# STM32F103T8.net
KiCad netlist of a schematic drawn in Altium Designer
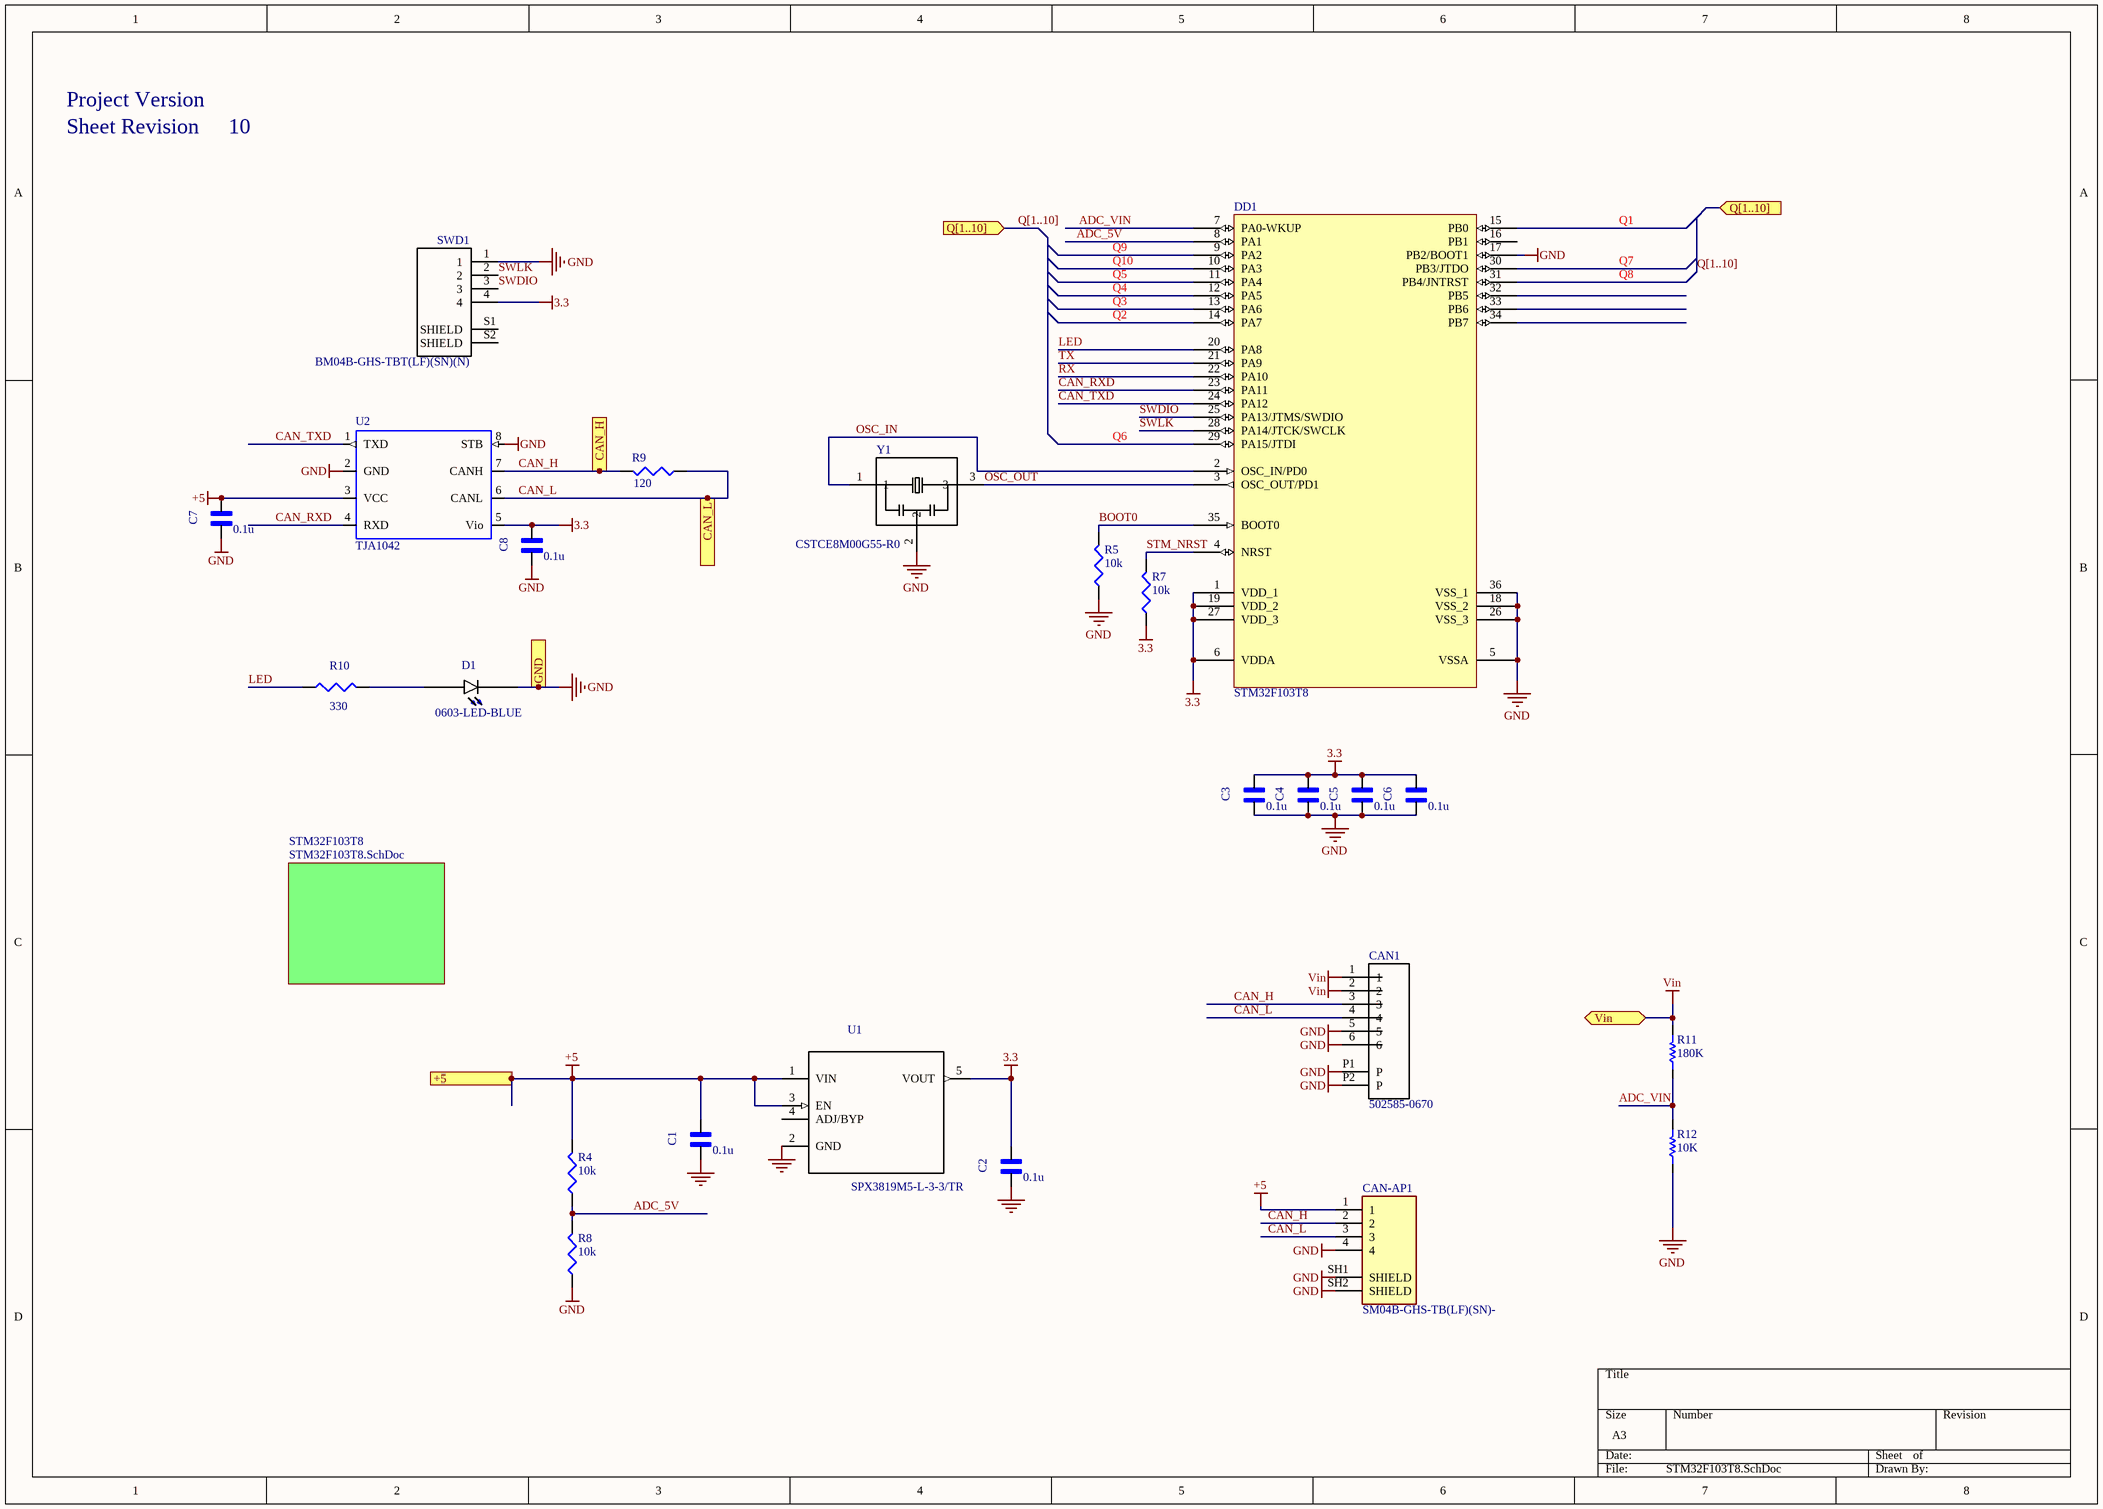
[diagram p0: STM32F103T8.SchDoc]

(export (version "E")
  (design (tool "Eeschema 10.0.6"))
  (components
    (comp (ref "C1")
      (value "0.1u")
      (footprint "*CAPC1608X90")
      (description "Cap Thin Film 0.1uf 50v 0603")
      (fields (field (name "MF") "AVX") (field (name "MP") "GX035C104MAT2-500"))
      (libsource (lib "lib") (part "GX035C104MAT2-500"))
    )
    (comp (ref "C2")
      (value "0.1u")
      (footprint "*CAPC1608X90")
      (description "Cap Thin Film 0.1uf 50v 0603")
      (fields (field (name "MF") "AVX") (field (name "MP") "GX035C104MAT2-500"))
      (libsource (lib "lib") (part "GX035C104MAT2-500"))
    )
    (comp (ref "C3")
      (value "0.1u")
      (footprint "*CAPC1608X90")
      (description "Cap Thin Film 0.1uf 50v 0603")
      (fields (field (name "MF") "AVX") (field (name "MP") "GX035C104MAT2-500 or CL10B104JB8NNNC"))
      (libsource (lib "lib") (part "GX035C104MAT2-500"))
    )
    (comp (ref "C4")
      (value "0.1u")
      (footprint "*CAPC1608X90")
      (description "Cap Thin Film 0.1uf 50v 0603")
      (fields (field (name "MF") "AVX") (field (name "MP") "GX035C104MAT2-500 or CL10B104JB8NNNC"))
      (libsource (lib "lib") (part "GX035C104MAT2-500"))
    )
    (comp (ref "C5")
      (value "0.1u")
      (footprint "*CAPC1608X90")
      (description "Cap Thin Film 0.1uf 50v 0603")
      (fields (field (name "MF") "AVX") (field (name "MP") "GX035C104MAT2-500 or CL10B104JB8NNNC"))
      (libsource (lib "lib") (part "GX035C104MAT2-500"))
    )
    (comp (ref "C6")
      (value "0.1u")
      (footprint "*CAPC1608X90")
      (description "Cap Thin Film 0.1uf 50v 0603")
      (fields (field (name "MF") "AVX") (field (name "MP") "GX035C104MAT2-500 or CL10B104JB8NNNC"))
      (libsource (lib "lib") (part "GX035C104MAT2-500"))
    )
    (comp (ref "C7")
      (value "0.1u")
      (footprint "*CAPC1608X90")
      (description "Cap Thin Film 0.1uf 50v 0603")
      (fields (field (name "MF") "AVX") (field (name "MP") "GX035C104MAT2-500 or CL10B104JB8NNNC"))
      (libsource (lib "lib") (part "GX035C104MAT2-500"))
    )
    (comp (ref "C8")
      (value "0.1u")
      (footprint "*CAPC1608X90")
      (description "Cap Thin Film 0.1uf 50v 0603")
      (fields (field (name "MF") "AVX") (field (name "MP") "GX035C104MAT2-500 or CL10B104JB8NNNC"))
      (libsource (lib "lib") (part "GX035C104MAT2-500"))
    )
    (comp (ref "CAN-AP1")
      (value "SM04B-GHS-TB(LF)(SN)-")
      (footprint "JST_SM04B-GHS-TB(LF)(SN)-")
      (description "Connector Header Surface Mount, Right Angle 4 position 0.049 _1.25mm_")
      (fields (field (name "MP") "SM04B-GHS-TB(LF)(SN)") (field (name "MF") "JST Sales"))
      (libsource (lib "lib") (part "SM04B-GHS-TB(LF)(SN)-"))
    )
    (comp (ref "CAN1")
      (value "502585-0670")
      (footprint "MOLEX_502585-0670")
      (fields (field (name "MF") "Molex"))
      (libsource (lib "lib") (part "502585-0670"))
    )
    (comp (ref "D1")
      (value "0603-LED-BLUE")
      (footprint "*LEDM1608X80_LTE-C1906R-14(Primary)")
      (description "LED IrLED Chip LED 2-Pin SMD T/R")
      (libsource (lib "lib") (part "LTE-C1906R-14"))
    )
    (comp (ref "DD1")
      (value "STM32F103T8")
      (footprint "*QFN50P600X600X100-37N")
      (description "STM32F103T8U6, Микроконтроллер 32BIT ARM 64K FLASH [VFQFPN-36]")
      (fields (field (name "MF") "STM") (field (name "MP") "STM32F103T8U6"))
      (libsource (lib "lib") (part "STM32F103T8"))
    )
    (comp (ref "R4")
      (value "10k")
      (footprint "J1-0603")
      (description "10 kOhms 1 0.1 W 1 10 W Chip Resistor 0603 1608 Metric Thick Film")
      (fields (field (name "MF") "Yageo or NXP") (field (name "MP") "10K 1% 0603"))
      (libsource (lib "CAN_NODE_MINI") (part "RC0603FR-0710KL"))
    )
    (comp (ref "R5")
      (value "10k")
      (footprint "J1-0603")
      (description "10 kOhms 1 0.1 W 1 10 W Chip Resistor 0603 1608 Metric Thick Film")
      (fields (field (name "MF") "Yageo or NXP") (field (name "MP") "10K 1% 0603"))
      (libsource (lib "CAN_NODE_MINI") (part "RC0603FR-0710KL"))
    )
    (comp (ref "R7")
      (value "10k")
      (footprint "J1-0603")
      (description "10 kOhms 1 0.1 W 1 10 W Chip Resistor 0603 1608 Metric Thick Film")
      (fields (field (name "MF") "Yageo or NXP") (field (name "MP") "10K 1% 0603"))
      (libsource (lib "CAN_NODE_MINI") (part "RC0603FR-0710KL"))
    )
    (comp (ref "R8")
      (value "10k")
      (footprint "J1-0603")
      (description "10 kOhms 1 0.1 W 1 10 W Chip Resistor 0603 1608 Metric Thick Film")
      (fields (field (name "MF") "Yageo or NXP") (field (name "MP") "10K 1% 0603"))
      (libsource (lib "CAN_NODE_MINI") (part "RC0603FR-0710KL"))
    )
    (comp (ref "R9")
      (value "120")
      (footprint "J1-0603")
      (description "120 Ohms 1 0.1 W 1 10 W Chip Resistor 0603 1608 Metric Thick Film")
      (fields (field (name "MP") "RC0603FR-07120RL") (field (name "Comment") "Res3"))
      (libsource (lib "Miscellaneous Devices") (part "Res3"))
    )
    (comp (ref "R10")
      (value "330")
      (footprint "J1-0603")
      (description "Resistor")
      (fields (field (name "MP") "RC0603FR-07330RL") (field (name "Comment") "Res3"))
      (libsource (lib "Miscellaneous Devices") (part "Res3"))
    )
    (comp (ref "R11")
      (value "180K")
      (footprint "RES 0603 (1608X06L)")
      (description "Resistor")
      (fields (field (name "TOLERANCE") "5%") (field (name "POWER") "1/8 W"))
      (libsource (lib "R2T Team Library") (part "Resistor"))
    )
    (comp (ref "R12")
      (value "10K")
      (footprint "RES 0603 (1608X06L)")
      (description "Resistor")
      (fields (field (name "TOLERANCE") "5%") (field (name "POWER") "1/8 W"))
      (libsource (lib "R2T Team Library") (part "Resistor"))
    )
    (comp (ref "SWD1")
      (value "BM04B-GHS-TBT(LF)(SN)(N)")
      (footprint "JST_BM04B-GHS-holes")
      (description "Conn Shrouded Header HDR 4 POS 1.25mm Solder ST SMD Reel")
      (fields (field (name "MF") "JST Sales") (field (name "MP") "SM04B-GHS-TB(LF)(SN)"))
      (libsource (lib "lib") (part "BM04B-GHS-TBT(LF)(SN)(N)"))
    )
    (comp (ref "U1")
      (value "SPX3819M5-L-3-3/TR")
      (footprint "*SOT95P280X145-5N")
      (description "Low Dropout Voltage Regulator, Adjustable 0.5A, В±1%, 2.5 to 16 Vin, 5-Pin SOT-23")
      (fields (field (name "MF") "MaxLinear, Inc."))
      (libsource (lib "DC_DC") (part "SPX3819M5-L"))
    )
    (comp (ref "U2")
      (value "TJA1042")
      (footprint "SOT782-1")
      (description "1/1 Transceiver Half CANbus 8-SO")
      (fields (field (name "MF") "NXP USA"))
      (libsource (lib "lib") (part "TJA1042"))
    )
    (comp (ref "Y1")
      (value "CSTCE8M00G55-R0")
      (footprint "*OSC_CSTCE8M00G55-R0")
      (description "Ceramic Resonator 8MHz ??0.5% _Tol_ ??0.2% _Stability_ 33pF 40Ohm 3-Pin CSMD T/R")
      (fields (field (name "MF") "Murata"))
      (libsource (lib "DC_DC") (part "CSTCE8M00G55-R0"))
    )
  )
  (nets
    (net (code "1") (name "+5") (class "Default")
      (node (ref "C1") (pin "1") (pinfunction "1_1") (pintype "passive"))
      (node (ref "C7") (pin "1") (pinfunction "1_1") (pintype "passive"))
      (node (ref "CAN-AP1") (pin "1") (pinfunction "1_1") (pintype "passive"))
      (node (ref "R4") (pin "2") (pinfunction "2_2") (pintype "passive"))
      (node (ref "U1") (pin "1") (pinfunction "VIN_1") (pintype "power_in"))
      (node (ref "U1") (pin "3") (pinfunction "EN_3") (pintype "input"))
      (node (ref "U2") (pin "3") (pinfunction "VCC_3") (pintype "power_in"))
    )
    (net (code "2") (name "/ADC_5V") (class "Default")
      (node (ref "DD1") (pin "8") (pinfunction "PA1_8") (pintype "bidirectional"))
      (node (ref "R4") (pin "1") (pinfunction "1_1") (pintype "passive"))
      (node (ref "R8") (pin "2") (pinfunction "2_2") (pintype "passive"))
    )
    (net (code "3") (name "/ADC_VIN") (class "Default")
      (node (ref "DD1") (pin "7") (pinfunction "PA0-WKUP_7") (pintype "bidirectional"))
      (node (ref "R11") (pin "1") (pinfunction "1_1") (pintype "passive"))
      (node (ref "R12") (pin "2") (pinfunction "2_2") (pintype "passive"))
    )
    (net (code "4") (name "/BOOT0") (class "Default")
      (node (ref "DD1") (pin "35") (pinfunction "BOOT0_35") (pintype "input"))
      (node (ref "R5") (pin "2") (pinfunction "2_2") (pintype "passive"))
    )
    (net (code "5") (name "/CAN_H") (class "Default")
      (node (ref "CAN-AP1") (pin "2") (pinfunction "2_2") (pintype "passive"))
      (node (ref "CAN1") (pin "3") (pinfunction "3_3") (pintype "passive"))
      (node (ref "R9") (pin "2") (pinfunction "2_2") (pintype "passive"))
      (node (ref "U2") (pin "7") (pinfunction "CANH_7") (pintype "bidirectional"))
    )
    (net (code "6") (name "/CAN_L") (class "Default")
      (node (ref "CAN-AP1") (pin "3") (pinfunction "3_3") (pintype "passive"))
      (node (ref "CAN1") (pin "4") (pinfunction "4_4") (pintype "passive"))
      (node (ref "R9") (pin "1") (pinfunction "1_1") (pintype "passive"))
      (node (ref "U2") (pin "6") (pinfunction "CANL_6") (pintype "bidirectional"))
    )
    (net (code "7") (name "/CAN_RXD") (class "Default")
      (node (ref "DD1") (pin "23") (pinfunction "PA11_23") (pintype "bidirectional"))
      (node (ref "U2") (pin "4") (pinfunction "RXD_4") (pintype "bidirectional"))
    )
    (net (code "8") (name "/CAN_TXD") (class "Default")
      (node (ref "DD1") (pin "24") (pinfunction "PA12_24") (pintype "bidirectional"))
      (node (ref "U2") (pin "1") (pinfunction "TXD_1") (pintype "output"))
    )
    (net (code "9") (name "/LED") (class "Default")
      (node (ref "DD1") (pin "20") (pinfunction "PA8_20") (pintype "bidirectional"))
      (node (ref "R10") (pin "1") (pinfunction "1_1") (pintype "passive"))
    )
    (net (code "10") (name "/OSC_IN") (class "Default")
      (node (ref "DD1") (pin "2") (pinfunction "OSC_IN/PD0_2") (pintype "input"))
      (node (ref "Y1") (pin "1") (pinfunction "1_1") (pintype "passive"))
    )
    (net (code "11") (name "/OSC_OUT") (class "Default")
      (node (ref "DD1") (pin "3") (pinfunction "OSC_OUT/PD1_3") (pintype "output"))
      (node (ref "Y1") (pin "3") (pinfunction "3_3") (pintype "passive"))
    )
    (net (code "12") (name "/Q1") (class "Default")
      (node (ref "DD1") (pin "15") (pinfunction "PB0_15") (pintype "bidirectional"))
    )
    (net (code "13") (name "/Q2") (class "Default")
      (node (ref "DD1") (pin "14") (pinfunction "PA7_14") (pintype "bidirectional"))
    )
    (net (code "14") (name "/Q3") (class "Default")
      (node (ref "DD1") (pin "13") (pinfunction "PA6_13") (pintype "bidirectional"))
    )
    (net (code "15") (name "/Q4") (class "Default")
      (node (ref "DD1") (pin "12") (pinfunction "PA5_12") (pintype "bidirectional"))
    )
    (net (code "16") (name "/Q5") (class "Default")
      (node (ref "DD1") (pin "11") (pinfunction "PA4_11") (pintype "bidirectional"))
    )
    (net (code "17") (name "/Q6") (class "Default")
      (node (ref "DD1") (pin "29") (pinfunction "PA15/JTDI_29") (pintype "bidirectional"))
    )
    (net (code "18") (name "/Q7") (class "Default")
      (node (ref "DD1") (pin "30") (pinfunction "PB3/JTDO_30") (pintype "bidirectional"))
    )
    (net (code "19") (name "/Q8") (class "Default")
      (node (ref "DD1") (pin "31") (pinfunction "PB4/JNTRST_31") (pintype "bidirectional"))
    )
    (net (code "20") (name "/Q9") (class "Default")
      (node (ref "DD1") (pin "9") (pinfunction "PA2_9") (pintype "bidirectional"))
    )
    (net (code "21") (name "/Q10") (class "Default")
      (node (ref "DD1") (pin "10") (pinfunction "PA3_10") (pintype "bidirectional"))
    )
    (net (code "23") (name "/RX") (class "Default")
      (node (ref "DD1") (pin "22") (pinfunction "PA10_22") (pintype "bidirectional"))
    )
    (net (code "24") (name "/STM_NRST") (class "Default")
      (node (ref "DD1") (pin "4") (pinfunction "NRST_4") (pintype "bidirectional"))
      (node (ref "R7") (pin "2") (pinfunction "2_2") (pintype "passive"))
    )
    (net (code "25") (name "/SWDIO") (class "Default")
      (node (ref "DD1") (pin "25") (pinfunction "PA13/JTMS/SWDIO_25") (pintype "bidirectional"))
      (node (ref "SWD1") (pin "3") (pinfunction "3_3") (pintype "passive"))
    )
    (net (code "26") (name "/SWLK") (class "Default")
      (node (ref "DD1") (pin "28") (pinfunction "PA14/JTCK/SWCLK_28") (pintype "bidirectional"))
      (node (ref "SWD1") (pin "2") (pinfunction "2_2") (pintype "passive"))
    )
    (net (code "27") (name "/TX") (class "Default")
      (node (ref "DD1") (pin "21") (pinfunction "PA9_21") (pintype "bidirectional"))
    )
    (net (code "28") (name "3.3") (class "Default")
      (node (ref "C2") (pin "1") (pinfunction "1_1") (pintype "passive"))
      (node (ref "C3") (pin "1") (pinfunction "1_1") (pintype "passive"))
      (node (ref "C4") (pin "1") (pinfunction "1_1") (pintype "passive"))
      (node (ref "C5") (pin "1") (pinfunction "1_1") (pintype "passive"))
      (node (ref "C6") (pin "1") (pinfunction "1_1") (pintype "passive"))
      (node (ref "C8") (pin "1") (pinfunction "1_1") (pintype "passive"))
      (node (ref "DD1") (pin "1") (pinfunction "VDD_1_1") (pintype "power_in"))
      (node (ref "DD1") (pin "19") (pinfunction "VDD_2_19") (pintype "power_in"))
      (node (ref "DD1") (pin "27") (pinfunction "VDD_3_27") (pintype "power_in"))
      (node (ref "DD1") (pin "6") (pinfunction "VDDA_6") (pintype "power_in"))
      (node (ref "R7") (pin "1") (pinfunction "1_1") (pintype "passive"))
      (node (ref "SWD1") (pin "4") (pinfunction "4_4") (pintype "passive"))
      (node (ref "U1") (pin "5") (pinfunction "VOUT_5") (pintype "output"))
      (node (ref "U2") (pin "5") (pinfunction "Vio_5") (pintype "power_in"))
    )
    (net (code "29") (name "GND") (class "Default")
      (node (ref "C1") (pin "2") (pinfunction "2_2") (pintype "passive"))
      (node (ref "C2") (pin "2") (pinfunction "2_2") (pintype "passive"))
      (node (ref "C3") (pin "2") (pinfunction "2_2") (pintype "passive"))
      (node (ref "C4") (pin "2") (pinfunction "2_2") (pintype "passive"))
      (node (ref "C5") (pin "2") (pinfunction "2_2") (pintype "passive"))
      (node (ref "C6") (pin "2") (pinfunction "2_2") (pintype "passive"))
      (node (ref "C7") (pin "2") (pinfunction "2_2") (pintype "passive"))
      (node (ref "C8") (pin "2") (pinfunction "2_2") (pintype "passive"))
      (node (ref "CAN-AP1") (pin "4") (pinfunction "4_4") (pintype "passive"))
      (node (ref "CAN-AP1") (pin "SH1") (pinfunction "SHIELD_SH1") (pintype "power_in"))
      (node (ref "CAN-AP1") (pin "SH2") (pinfunction "SHIELD_SH2") (pintype "power_in"))
      (node (ref "CAN1") (pin "5") (pinfunction "5_5") (pintype "passive"))
      (node (ref "CAN1") (pin "6") (pinfunction "6_6") (pintype "passive"))
      (node (ref "CAN1") (pin "P1") (pinfunction "P_P1") (pintype "passive"))
      (node (ref "CAN1") (pin "P2") (pinfunction "P_P2") (pintype "passive"))
      (node (ref "D1") (pin "C") (pinfunction "C_C") (pintype "passive"))
      (node (ref "DD1") (pin "17") (pinfunction "PB2/BOOT1_17") (pintype "bidirectional"))
      (node (ref "DD1") (pin "18") (pinfunction "VSS_2_18") (pintype "power_in"))
      (node (ref "DD1") (pin "26") (pinfunction "VSS_3_26") (pintype "power_in"))
      (node (ref "DD1") (pin "36") (pinfunction "VSS_1_36") (pintype "power_in"))
      (node (ref "DD1") (pin "5") (pinfunction "VSSA_5") (pintype "power_in"))
      (node (ref "R12") (pin "1") (pinfunction "1_1") (pintype "passive"))
      (node (ref "R5") (pin "1") (pinfunction "1_1") (pintype "passive"))
      (node (ref "R8") (pin "1") (pinfunction "1_1") (pintype "passive"))
      (node (ref "SWD1") (pin "1") (pinfunction "1_1") (pintype "passive"))
      (node (ref "U1") (pin "2") (pinfunction "GND_2") (pintype "passive"))
      (node (ref "U2") (pin "2") (pinfunction "GND_2") (pintype "power_in"))
      (node (ref "U2") (pin "8") (pinfunction "STB_8") (pintype "input"))
      (node (ref "Y1") (pin "2") (pinfunction "2_2") (pintype "power_in"))
    )
    (net (code "30") (name "Net-(D1-PadA)") (class "Default")
      (node (ref "D1") (pin "A") (pinfunction "A_A") (pintype "passive"))
      (node (ref "R10") (pin "2") (pinfunction "2_2") (pintype "passive"))
    )
    (net (code "31") (name "Vin") (class "Default")
      (node (ref "CAN1") (pin "1") (pinfunction "1_1") (pintype "passive"))
      (node (ref "CAN1") (pin "2") (pinfunction "2_2") (pintype "passive"))
      (node (ref "R11") (pin "2") (pinfunction "2_2") (pintype "passive"))
    )
    (net (code "32") (name "unconnected-(DD1-PB1-Pad16)") (class "Default")
      (node (ref "DD1") (pin "16") (pinfunction "PB1_16") (pintype "bidirectional"))
    )
    (net (code "33") (name "unconnected-(DD1-PB5-Pad32)") (class "Default")
      (node (ref "DD1") (pin "32") (pinfunction "PB5_32") (pintype "bidirectional"))
    )
    (net (code "34") (name "unconnected-(DD1-PB6-Pad33)") (class "Default")
      (node (ref "DD1") (pin "33") (pinfunction "PB6_33") (pintype "bidirectional"))
    )
    (net (code "35") (name "unconnected-(DD1-PB7-Pad34)") (class "Default")
      (node (ref "DD1") (pin "34") (pinfunction "PB7_34") (pintype "bidirectional"))
    )
    (net (code "36") (name "unconnected-(SWD1-SHIELD-PadS1)") (class "Default")
      (node (ref "SWD1") (pin "S1") (pinfunction "SHIELD_S1") (pintype "passive"))
    )
    (net (code "37") (name "unconnected-(SWD1-SHIELD-PadS2)") (class "Default")
      (node (ref "SWD1") (pin "S2") (pinfunction "SHIELD_S2") (pintype "passive"))
    )
    (net (code "38") (name "unconnected-(U1-ADJ{slash}BYP-Pad4)") (class "Default")
      (node (ref "U1") (pin "4") (pinfunction "ADJ/BYP_4") (pintype "passive"))
    )
  )
)
